# 3_-_Sense2GoL_V1_2_Debugger.net
KiCad netlist of a schematic drawn in Altium Designer
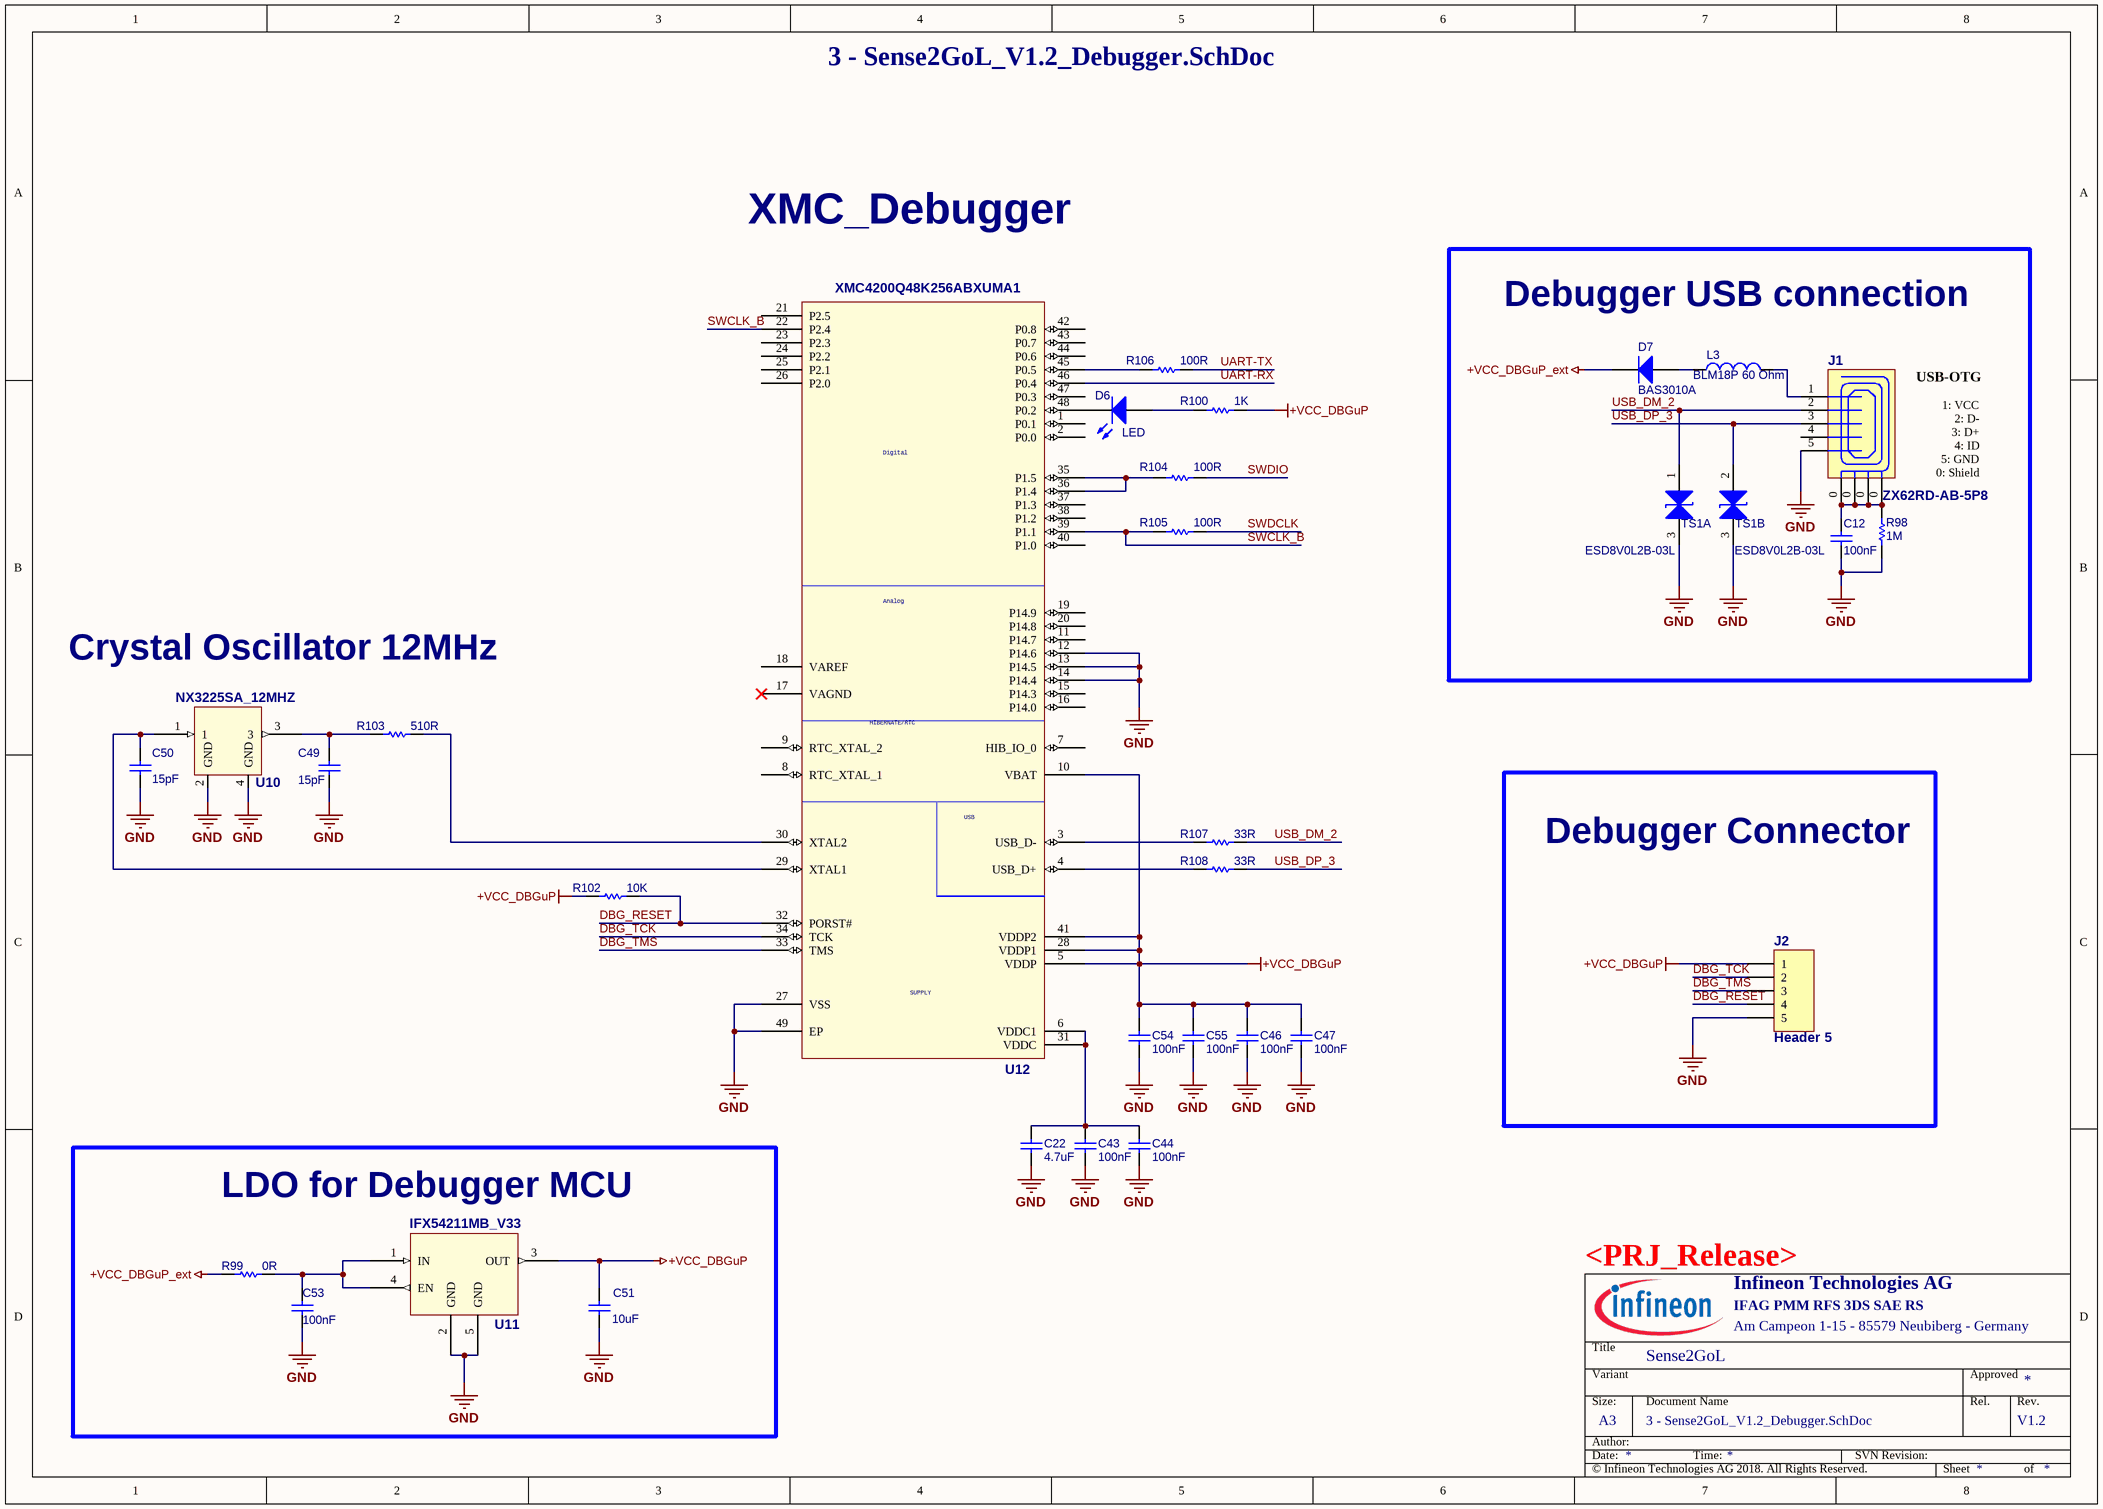
[diagram p0: 3 - Sense2GoL_V1.2_Debugger.SchDoc]

(export (version "E")
  (design (tool "Eeschema 10.0.6"))
  (components
    (comp (ref "C12")
      (value "100nF")
      (footprint "0402_DURAC")
      (description "Capacitor")
      (fields (field (name "Comment") "Cap") (field (name "PUBLISHER") "Altium Limited"))
      (libsource (lib "Miscellaneous Devices") (part "Cap"))
    )
    (comp (ref "C22")
      (value "4.7uF")
      (footprint "0402_DURAC")
      (description "Capacitor")
      (fields (field (name "Comment") "Cap") (field (name "PUBLISHER") "Altium Limited"))
      (libsource (lib "Miscellaneous Devices") (part "Cap"))
    )
    (comp (ref "C43")
      (value "100nF")
      (footprint "0402_DURAC")
      (description "Capacitor")
      (fields (field (name "Comment") "Cap") (field (name "PUBLISHER") "Altium Limited"))
      (libsource (lib "Miscellaneous Devices") (part "Cap"))
    )
    (comp (ref "C44")
      (value "100nF")
      (footprint "0402_DURAC")
      (description "Capacitor")
      (fields (field (name "Comment") "Cap") (field (name "PUBLISHER") "Altium Limited"))
      (libsource (lib "Miscellaneous Devices") (part "Cap"))
    )
    (comp (ref "C46")
      (value "100nF")
      (footprint "0402_DURAC")
      (description "Capacitor")
      (fields (field (name "Comment") "Cap") (field (name "PUBLISHER") "Altium Limited"))
      (libsource (lib "Miscellaneous Devices") (part "Cap"))
    )
    (comp (ref "C47")
      (value "100nF")
      (footprint "0402_DURAC")
      (description "Capacitor")
      (fields (field (name "Comment") "Cap") (field (name "PUBLISHER") "Altium Limited"))
      (libsource (lib "Miscellaneous Devices") (part "Cap"))
    )
    (comp (ref "C49")
      (value "15pF")
      (footprint "0402_DURAC")
      (description "Capacitor")
      (fields (field (name "Comment") "Cap") (field (name "PUBLISHER") "Altium Limited"))
      (libsource (lib "Miscellaneous Devices") (part "Cap"))
    )
    (comp (ref "C50")
      (value "15pF")
      (footprint "0402_DURAC")
      (description "Capacitor")
      (fields (field (name "Comment") "Cap") (field (name "PUBLISHER") "Altium Limited"))
      (libsource (lib "Miscellaneous Devices") (part "Cap"))
    )
    (comp (ref "C51")
      (value "10uF")
      (footprint "0402_DURAC")
      (description "Capacitor")
      (fields (field (name "Comment") "Cap") (field (name "PUBLISHER") "Altium Limited"))
      (libsource (lib "Miscellaneous Devices") (part "Cap"))
    )
    (comp (ref "C53")
      (value "100nF")
      (footprint "0402_DURAC")
      (description "Capacitor")
      (fields (field (name "Comment") "Cap") (field (name "PUBLISHER") "Altium Limited"))
      (libsource (lib "Miscellaneous Devices") (part "Cap"))
    )
    (comp (ref "C54")
      (value "100nF")
      (footprint "0402_DURAC")
      (description "Capacitor")
      (fields (field (name "Comment") "Cap") (field (name "PUBLISHER") "Altium Limited"))
      (libsource (lib "Miscellaneous Devices") (part "Cap"))
    )
    (comp (ref "C55")
      (value "100nF")
      (footprint "0402_DURAC")
      (description "Capacitor")
      (fields (field (name "Comment") "Cap") (field (name "PUBLISHER") "Altium Limited"))
      (libsource (lib "Miscellaneous Devices") (part "Cap"))
    )
    (comp (ref "D6")
      (value "LED")
      (footprint "LED_0201")
      (description "Typical INFRARED GaAs LED")
      (fields (field (name "PUBLISHER") "Altium Limited"))
      (libsource (lib "Miscellaneous Devices") (part "LED"))
    )
    (comp (ref "D7")
      (value "BAS3010A")
      (footprint "SOD323")
      (description "Default Diode")
      (fields (field (name "PUBLISHER") "Altium Limited"))
      (libsource (lib "Miscellaneous Devices") (part "Diode"))
    )
    (comp (ref "J1")
      (value "ZX62RD-AB-5P8")
      (footprint "MICRO_AB_ZX62")
      (description "USB Micro AB")
      (libsource (lib "Miscellaneous Devices") (part "USB Micro AB"))
    )
    (comp (ref "J2")
      (value "Header 5")
      (footprint "CON_5PIN_254P")
      (description "Header, 5-Pin")
      (fields (field (name "PUBLISHER") "Altium Limited"))
      (libsource (lib "Miscellaneous Connectors") (part "Header 5"))
    )
    (comp (ref "L3")
      (value "BLM18P 60 Ohm")
      (footprint "L_0603")
      (libsource (lib "Miscellaneous Devices") (part "Ferrite Bead"))
    )
    (comp (ref "R98")
      (value "1M")
      (footprint "0402_R")
      (description "Resistor")
      (fields (field (name "Comment") "Res1") (field (name "PUBLISHER") "Altium Limited"))
      (libsource (lib "Miscellaneous Devices") (part "Res1"))
    )
    (comp (ref "R99")
      (value "0R")
      (footprint "0402_R")
      (description "Resistor")
      (fields (field (name "Comment") "Res1") (field (name "PUBLISHER") "Altium Limited"))
      (libsource (lib "Miscellaneous Devices") (part "Res1"))
    )
    (comp (ref "R100")
      (value "1K")
      (footprint "R_0201")
      (description "Resistor")
      (fields (field (name "Comment") "Res1") (field (name "PUBLISHER") "Altium Limited"))
      (libsource (lib "Miscellaneous Devices") (part "Res1"))
    )
    (comp (ref "R102")
      (value "10K")
      (footprint "0402_R")
      (description "Resistor")
      (fields (field (name "Comment") "Res1") (field (name "PUBLISHER") "Altium Limited"))
      (libsource (lib "Miscellaneous Devices") (part "Res1"))
    )
    (comp (ref "R103")
      (value "510R")
      (footprint "0402_R")
      (description "Resistor")
      (fields (field (name "Comment") "Res1") (field (name "PUBLISHER") "Altium Limited"))
      (libsource (lib "Miscellaneous Devices") (part "Res1"))
    )
    (comp (ref "R104")
      (value "100R")
      (footprint "0402_R")
      (description "Resistor")
      (fields (field (name "Comment") "Res1") (field (name "PUBLISHER") "Altium Limited"))
      (libsource (lib "Miscellaneous Devices") (part "Res1"))
    )
    (comp (ref "R105")
      (value "100R")
      (footprint "0402_R")
      (description "Resistor")
      (fields (field (name "Comment") "Res1") (field (name "PUBLISHER") "Altium Limited"))
      (libsource (lib "Miscellaneous Devices") (part "Res1"))
    )
    (comp (ref "R106")
      (value "100R")
      (footprint "0402_R")
      (description "Resistor")
      (fields (field (name "Comment") "Res1") (field (name "PUBLISHER") "Altium Limited"))
      (libsource (lib "Miscellaneous Devices") (part "Res1"))
    )
    (comp (ref "R107")
      (value "33R")
      (footprint "0402_R")
      (description "Resistor")
      (fields (field (name "Comment") "Res1") (field (name "PUBLISHER") "Altium Limited"))
      (libsource (lib "Miscellaneous Devices") (part "Res1"))
    )
    (comp (ref "R108")
      (value "33R")
      (footprint "0402_R")
      (description "Resistor")
      (fields (field (name "Comment") "Res1") (field (name "PUBLISHER") "Altium Limited"))
      (libsource (lib "Miscellaneous Devices") (part "Res1"))
    )
    (comp (ref "TS1")
      (value "ESD8V0L2B-03L")
      (footprint "ESD8VOL2B")
      (description "TVS Diode dual")
      (libsource (lib "Miscellaneous Devices") (part "Diode dual"))
    )
    (comp (ref "U10")
      (value "NX3225SA_12MHZ")
      (footprint "NX3225SA")
      (description "NX3225SA-12.000M-STD-CRS-2")
      (libsource (lib "Miscellaneous Devices") (part "NX3225SA_12MHZ"))
    )
    (comp (ref "U11")
      (value "IFX54211MB_V33")
      (footprint "inf-pg-sct595v")
      (libsource (lib "Integrated Circuits") (part "IFX54211MB_V33"))
    )
    (comp (ref "U12")
      (value "XMC4200Q48K256ABXUMA1")
      (footprint "inf-pg-vqfn-48-_-5200x5200tp_n")
      (libsource (lib "Integrated Circuits") (part "XMC4200_VQFN48"))
    )
  )
  (nets
    (net (code "1") (name "+VCC_DBGuP") (class "Default")
      (node (ref "C46") (pin "2") (pinfunction "2_2") (pintype "passive"))
      (node (ref "C47") (pin "2") (pinfunction "2_2") (pintype "passive"))
      (node (ref "C51") (pin "2") (pinfunction "2_2") (pintype "passive"))
      (node (ref "C54") (pin "2") (pinfunction "2_2") (pintype "passive"))
      (node (ref "C55") (pin "2") (pinfunction "2_2") (pintype "passive"))
      (node (ref "J2") (pin "1") (pinfunction "1_1") (pintype "passive"))
      (node (ref "R100") (pin "1") (pinfunction "1_1") (pintype "passive"))
      (node (ref "R102") (pin "1") (pinfunction "1_1") (pintype "passive"))
      (node (ref "U11") (pin "3") (pinfunction "OUT_3") (pintype "output"))
      (node (ref "U12") (pin "10") (pinfunction "VBAT_10") (pintype "power_in"))
      (node (ref "U12") (pin "28") (pinfunction "VDDP1_28") (pintype "power_in"))
      (node (ref "U12") (pin "41") (pinfunction "VDDP2_41") (pintype "power_in"))
      (node (ref "U12") (pin "5") (pinfunction "VDDP_5") (pintype "power_in"))
    )
    (net (code "2") (name "+VCC_DBGuP_ext") (class "Default")
      (node (ref "D7") (pin "2") (pinfunction "K_2") (pintype "passive"))
      (node (ref "R99") (pin "2") (pinfunction "2_2") (pintype "passive"))
    )
    (net (code "3") (name "/DBG_RESET") (class "Default")
      (node (ref "J2") (pin "4") (pinfunction "4_4") (pintype "passive"))
      (node (ref "R102") (pin "2") (pinfunction "2_2") (pintype "passive"))
      (node (ref "U12") (pin "32") (pinfunction "PORST#_32") (pintype "bidirectional"))
    )
    (net (code "4") (name "/DBG_TCK") (class "Default")
      (node (ref "J2") (pin "2") (pinfunction "2_2") (pintype "passive"))
      (node (ref "U12") (pin "34") (pinfunction "TCK_34") (pintype "bidirectional"))
    )
    (net (code "5") (name "/DBG_TMS") (class "Default")
      (node (ref "J2") (pin "3") (pinfunction "3_3") (pintype "passive"))
      (node (ref "U12") (pin "33") (pinfunction "TMS_33") (pintype "bidirectional"))
    )
    (net (code "6") (name "/SWCLK_B") (class "Default")
      (node (ref "R105") (pin "1") (pinfunction "1_1") (pintype "passive"))
      (node (ref "U12") (pin "22") (pinfunction "P2.4_22") (pintype "passive"))
      (node (ref "U12") (pin "39") (pinfunction "P1.1_39") (pintype "bidirectional"))
    )
    (net (code "7") (name "/SWDCLK") (class "Default")
      (node (ref "R105") (pin "2") (pinfunction "2_2") (pintype "passive"))
    )
    (net (code "8") (name "/SWDIO") (class "Default")
      (node (ref "R104") (pin "2") (pinfunction "2_2") (pintype "passive"))
    )
    (net (code "9") (name "/UART-RX") (class "Default")
      (node (ref "U12") (pin "46") (pinfunction "P0.4_46") (pintype "bidirectional"))
    )
    (net (code "10") (name "/UART-TX") (class "Default")
      (node (ref "R106") (pin "2") (pinfunction "2_2") (pintype "passive"))
    )
    (net (code "11") (name "/USB_DM_2") (class "Default")
      (node (ref "J1") (pin "2") (pinfunction "D-_2") (pintype "passive"))
      (node (ref "R107") (pin "2") (pinfunction "2_2") (pintype "passive"))
      (node (ref "TS1") (pin "1") (pinfunction "1_1") (pintype "passive"))
    )
    (net (code "12") (name "/USB_DP_3") (class "Default")
      (node (ref "J1") (pin "3") (pinfunction "D+_3") (pintype "passive"))
      (node (ref "R108") (pin "2") (pinfunction "2_2") (pintype "passive"))
      (node (ref "TS1") (pin "2") (pinfunction "2_2") (pintype "passive"))
    )
    (net (code "13") (name "GND") (class "Default")
      (node (ref "C12") (pin "2") (pinfunction "2_2") (pintype "passive"))
      (node (ref "C22") (pin "2") (pinfunction "2_2") (pintype "passive"))
      (node (ref "C43") (pin "1") (pinfunction "1_1") (pintype "passive"))
      (node (ref "C44") (pin "1") (pinfunction "1_1") (pintype "passive"))
      (node (ref "C46") (pin "1") (pinfunction "1_1") (pintype "passive"))
      (node (ref "C47") (pin "1") (pinfunction "1_1") (pintype "passive"))
      (node (ref "C49") (pin "2") (pinfunction "2_2") (pintype "passive"))
      (node (ref "C50") (pin "2") (pinfunction "2_2") (pintype "passive"))
      (node (ref "C51") (pin "1") (pinfunction "1_1") (pintype "passive"))
      (node (ref "C53") (pin "2") (pinfunction "2_2") (pintype "passive"))
      (node (ref "C54") (pin "1") (pinfunction "1_1") (pintype "passive"))
      (node (ref "C55") (pin "1") (pinfunction "1_1") (pintype "passive"))
      (node (ref "J1") (pin "5") (pinfunction "GND_5") (pintype "passive"))
      (node (ref "J2") (pin "5") (pinfunction "5_5") (pintype "passive"))
      (node (ref "R98") (pin "1") (pinfunction "1_1") (pintype "passive"))
      (node (ref "TS1") (pin "3") (pinfunction "3_3") (pintype "passive"))
      (node (ref "U10") (pin "2") (pinfunction "GND_2") (pintype "power_in"))
      (node (ref "U10") (pin "4") (pinfunction "GND_4") (pintype "power_in"))
      (node (ref "U11") (pin "2") (pinfunction "GND_2") (pintype "power_in"))
      (node (ref "U11") (pin "5") (pinfunction "GND_5") (pintype "power_in"))
      (node (ref "U12") (pin "12") (pinfunction "P14.6_12") (pintype "bidirectional"))
      (node (ref "U12") (pin "13") (pinfunction "P14.5_13") (pintype "bidirectional"))
      (node (ref "U12") (pin "14") (pinfunction "P14.4_14") (pintype "bidirectional"))
      (node (ref "U12") (pin "27") (pinfunction "VSS_27") (pintype "power_in"))
      (node (ref "U12") (pin "49") (pinfunction "EP_49") (pintype "power_in"))
    )
    (net (code "14") (name "Net-(C49-Pad1)") (class "Default")
      (node (ref "C49") (pin "1") (pinfunction "1_1") (pintype "passive"))
      (node (ref "R103") (pin "1") (pinfunction "1_1") (pintype "passive"))
      (node (ref "U10") (pin "3") (pinfunction "3_3") (pintype "output"))
    )
    (net (code "15") (name "Net-(D6-A)") (class "Default")
      (node (ref "D6") (pin "1") (pinfunction "A_1") (pintype "passive"))
      (node (ref "R100") (pin "2") (pinfunction "2_2") (pintype "passive"))
    )
    (net (code "16") (name "Net-(D6-K)") (class "Default")
      (node (ref "D6") (pin "2") (pinfunction "K_2") (pintype "passive"))
      (node (ref "U12") (pin "48") (pinfunction "P0.2_48") (pintype "bidirectional"))
    )
    (net (code "17") (name "Net-(D7-A)") (class "Default")
      (node (ref "D7") (pin "1") (pinfunction "A_1") (pintype "passive"))
      (node (ref "L3") (pin "1") (pinfunction "1_1") (pintype "passive"))
    )
    (net (code "18") (name "Net-(J1-Shield)") (class "Default")
      (node (ref "C12") (pin "1") (pinfunction "1_1") (pintype "passive"))
      (node (ref "J1") (pin "0") (pinfunction "Shield_0") (pintype "passive"))
      (node (ref "R98") (pin "2") (pinfunction "2_2") (pintype "passive"))
    )
    (net (code "19") (name "Net-(J1-VCC)") (class "Default")
      (node (ref "J1") (pin "1") (pinfunction "VCC_1") (pintype "passive"))
      (node (ref "L3") (pin "2") (pinfunction "2_2") (pintype "passive"))
    )
    (net (code "20") (name "Net-(U11-EN)") (class "Default")
      (node (ref "C53") (pin "1") (pinfunction "1_1") (pintype "passive"))
      (node (ref "R99") (pin "1") (pinfunction "1_1") (pintype "passive"))
      (node (ref "U11") (pin "1") (pinfunction "IN_1") (pintype "input"))
      (node (ref "U11") (pin "4") (pinfunction "EN_4") (pintype "output"))
    )
    (net (code "21") (name "Net-(U12-P0.5)") (class "Default")
      (node (ref "R106") (pin "1") (pinfunction "1_1") (pintype "passive"))
      (node (ref "U12") (pin "45") (pinfunction "P0.5_45") (pintype "bidirectional"))
    )
    (net (code "22") (name "Net-(U12-P1.4)") (class "Default")
      (node (ref "R104") (pin "1") (pinfunction "1_1") (pintype "passive"))
      (node (ref "U12") (pin "35") (pinfunction "P1.5_35") (pintype "bidirectional"))
      (node (ref "U12") (pin "36") (pinfunction "P1.4_36") (pintype "bidirectional"))
    )
    (net (code "23") (name "Net-(U12-USB_D+)") (class "Default")
      (node (ref "R108") (pin "1") (pinfunction "1_1") (pintype "passive"))
      (node (ref "U12") (pin "4") (pinfunction "USB_D+_4") (pintype "bidirectional"))
    )
    (net (code "24") (name "Net-(U12-USB_D-)") (class "Default")
      (node (ref "R107") (pin "1") (pinfunction "1_1") (pintype "passive"))
      (node (ref "U12") (pin "3") (pinfunction "USB_D-_3") (pintype "bidirectional"))
    )
    (net (code "25") (name "Net-(U12-VDDC)") (class "Default")
      (node (ref "C22") (pin "1") (pinfunction "1_1") (pintype "passive"))
      (node (ref "C43") (pin "2") (pinfunction "2_2") (pintype "passive"))
      (node (ref "C44") (pin "2") (pinfunction "2_2") (pintype "passive"))
      (node (ref "U12") (pin "31") (pinfunction "VDDC_31") (pintype "power_in"))
      (node (ref "U12") (pin "6") (pinfunction "VDDC1_6") (pintype "power_in"))
    )
    (net (code "26") (name "Net-(U12-XTAL1)") (class "Default")
      (node (ref "C50") (pin "1") (pinfunction "1_1") (pintype "passive"))
      (node (ref "U10") (pin "1") (pinfunction "1_1") (pintype "input"))
      (node (ref "U12") (pin "29") (pinfunction "XTAL1_29") (pintype "bidirectional"))
    )
    (net (code "27") (name "Net-(U12-XTAL2)") (class "Default")
      (node (ref "R103") (pin "2") (pinfunction "2_2") (pintype "passive"))
      (node (ref "U12") (pin "30") (pinfunction "XTAL2_30") (pintype "bidirectional"))
    )
    (net (code "28") (name "unconnected-(J1-ID-Pad4)") (class "Default")
      (node (ref "J1") (pin "4") (pinfunction "ID_4") (pintype "passive"))
    )
    (net (code "29") (name "unconnected-(U12-HIB_IO_0-Pad7)") (class "Default")
      (node (ref "U12") (pin "7") (pinfunction "HIB_IO_0_7") (pintype "bidirectional"))
    )
    (net (code "30") (name "unconnected-(U12-P0.0-Pad2)") (class "Default")
      (node (ref "U12") (pin "2") (pinfunction "P0.0_2") (pintype "bidirectional"))
    )
    (net (code "31") (name "unconnected-(U12-P0.1-Pad1)") (class "Default")
      (node (ref "U12") (pin "1") (pinfunction "P0.1_1") (pintype "bidirectional"))
    )
    (net (code "32") (name "unconnected-(U12-P0.3-Pad47)") (class "Default")
      (node (ref "U12") (pin "47") (pinfunction "P0.3_47") (pintype "bidirectional"))
    )
    (net (code "33") (name "unconnected-(U12-P0.6-Pad44)") (class "Default")
      (node (ref "U12") (pin "44") (pinfunction "P0.6_44") (pintype "bidirectional"))
    )
    (net (code "34") (name "unconnected-(U12-P0.7-Pad43)") (class "Default")
      (node (ref "U12") (pin "43") (pinfunction "P0.7_43") (pintype "bidirectional"))
    )
    (net (code "35") (name "unconnected-(U12-P0.8-Pad42)") (class "Default")
      (node (ref "U12") (pin "42") (pinfunction "P0.8_42") (pintype "bidirectional"))
    )
    (net (code "36") (name "unconnected-(U12-P1.0-Pad40)") (class "Default")
      (node (ref "U12") (pin "40") (pinfunction "P1.0_40") (pintype "bidirectional"))
    )
    (net (code "37") (name "unconnected-(U12-P1.2-Pad38)") (class "Default")
      (node (ref "U12") (pin "38") (pinfunction "P1.2_38") (pintype "bidirectional"))
    )
    (net (code "38") (name "unconnected-(U12-P1.3-Pad37)") (class "Default")
      (node (ref "U12") (pin "37") (pinfunction "P1.3_37") (pintype "bidirectional"))
    )
    (net (code "39") (name "unconnected-(U12-P2.0-Pad26)") (class "Default")
      (node (ref "U12") (pin "26") (pinfunction "P2.0_26") (pintype "passive"))
    )
    (net (code "40") (name "unconnected-(U12-P2.1-Pad25)") (class "Default")
      (node (ref "U12") (pin "25") (pinfunction "P2.1_25") (pintype "passive"))
    )
    (net (code "41") (name "unconnected-(U12-P2.2-Pad24)") (class "Default")
      (node (ref "U12") (pin "24") (pinfunction "P2.2_24") (pintype "passive"))
    )
    (net (code "42") (name "unconnected-(U12-P2.3-Pad23)") (class "Default")
      (node (ref "U12") (pin "23") (pinfunction "P2.3_23") (pintype "passive"))
    )
    (net (code "43") (name "unconnected-(U12-P2.5-Pad21)") (class "Default")
      (node (ref "U12") (pin "21") (pinfunction "P2.5_21") (pintype "passive"))
    )
    (net (code "44") (name "unconnected-(U12-P14.0-Pad16)") (class "Default")
      (node (ref "U12") (pin "16") (pinfunction "P14.0_16") (pintype "bidirectional"))
    )
    (net (code "45") (name "unconnected-(U12-P14.3-Pad15)") (class "Default")
      (node (ref "U12") (pin "15") (pinfunction "P14.3_15") (pintype "bidirectional"))
    )
    (net (code "46") (name "unconnected-(U12-P14.7-Pad11)") (class "Default")
      (node (ref "U12") (pin "11") (pinfunction "P14.7_11") (pintype "bidirectional"))
    )
    (net (code "47") (name "unconnected-(U12-P14.8-Pad20)") (class "Default")
      (node (ref "U12") (pin "20") (pinfunction "P14.8_20") (pintype "bidirectional"))
    )
    (net (code "48") (name "unconnected-(U12-P14.9-Pad19)") (class "Default")
      (node (ref "U12") (pin "19") (pinfunction "P14.9_19") (pintype "bidirectional"))
    )
    (net (code "49") (name "unconnected-(U12-RTC_XTAL_1-Pad8)") (class "Default")
      (node (ref "U12") (pin "8") (pinfunction "RTC_XTAL_1_8") (pintype "bidirectional"))
    )
    (net (code "50") (name "unconnected-(U12-RTC_XTAL_2-Pad9)") (class "Default")
      (node (ref "U12") (pin "9") (pinfunction "RTC_XTAL_2_9") (pintype "bidirectional"))
    )
    (net (code "51") (name "unconnected-(U12-VAGND-Pad17)") (class "Default")
      (node (ref "U12") (pin "17") (pinfunction "VAGND_17") (pintype "power_in+no_connect"))
    )
    (net (code "52") (name "unconnected-(U12-VAREF-Pad18)") (class "Default")
      (node (ref "U12") (pin "18") (pinfunction "VAREF_18") (pintype "power_in"))
    )
  )
)
